# Debugger.net
KiCad netlist of a schematic drawn in Altium Designer
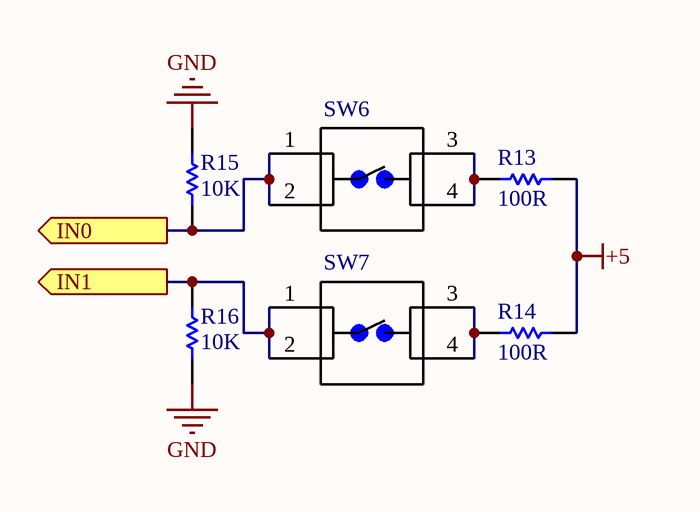
[diagram p0: Debugger.SchDoc]

(export (version "E")
  (design (tool "Eeschema 10.0.6"))
  (components
    (comp (ref "R13")
      (value "100R")
      (footprint "RESC0805(2012)_L")
      (description "100R 0.125W 1% 0805 (2012 Metric)  SMD")
      (fields (field (name "POWER") "0.125 W") (field (name "TOLERANCE") "1 %"))
      (libsource (lib "Altium Content Vault") (part "RES"))
    )
    (comp (ref "R14")
      (value "100R")
      (footprint "RESC0805(2012)_L")
      (description "100R 0.125W 1% 0805 (2012 Metric)  SMD")
      (fields (field (name "POWER") "0.125 W") (field (name "TOLERANCE") "1 %"))
      (libsource (lib "Altium Content Vault") (part "RES"))
    )
    (comp (ref "R15")
      (value "10K")
      (footprint "RESC0805(2012)_L")
      (description "10K2 0.125W 1% 0805 (2012 Metric)  SMD")
      (fields (field (name "TOLERANCE") "1 %") (field (name "POWER") "0.125 W"))
      (libsource (lib "Altium Content Vault") (part "RES"))
    )
    (comp (ref "R16")
      (value "10K")
      (footprint "RESC0805(2012)_L")
      (description "10K2 0.125W 1% 0805 (2012 Metric)  SMD")
      (fields (field (name "TOLERANCE") "1 %") (field (name "POWER") "0.125 W"))
      (libsource (lib "Altium Content Vault") (part "RES"))
    )
    (comp (ref "SW6")
      (value "1825910-7")
      (footprint "Switch 6mm 24V (NO)")
      (description "FSM4JAH=6MM TACT SWITCH, HIGH TEMP")
      (fields (field (name "MF") "TE Connectivity") (field (name "DIGI-KEY_PART_NUMBER") "450-1804-ND"))
      (libsource (lib "Husky Robotics Standard Library 2019-2020") (part "Switch 6mm 24V (NO)"))
    )
    (comp (ref "SW7")
      (value "1825910-7")
      (footprint "Switch 6mm 24V (NO)")
      (description "FSM4JAH=6MM TACT SWITCH, HIGH TEMP")
      (fields (field (name "MF") "TE Connectivity") (field (name "DIGI-KEY_PART_NUMBER") "450-1804-ND"))
      (libsource (lib "Husky Robotics Standard Library 2019-2020") (part "Switch 6mm 24V (NO)"))
    )
  )
  (nets
    (net (code "1") (name "+5") (class "Default")
      (node (ref "R13") (pin "1") (pinfunction "1_1") (pintype "passive"))
      (node (ref "R14") (pin "1") (pinfunction "1_1") (pintype "passive"))
    )
    (net (code "2") (name "/IN0") (class "Default")
      (node (ref "R15") (pin "1") (pinfunction "1_1") (pintype "passive"))
      (node (ref "SW6") (pin "1") (pinfunction "1_1") (pintype "passive"))
      (node (ref "SW6") (pin "2") (pinfunction "2_2") (pintype "passive"))
    )
    (net (code "3") (name "/IN1") (class "Default")
      (node (ref "R16") (pin "2") (pinfunction "2_2") (pintype "passive"))
      (node (ref "SW7") (pin "1") (pinfunction "1_1") (pintype "passive"))
      (node (ref "SW7") (pin "2") (pinfunction "2_2") (pintype "passive"))
    )
    (net (code "4") (name "GND") (class "Default")
      (node (ref "R15") (pin "2") (pinfunction "2_2") (pintype "passive"))
      (node (ref "R16") (pin "1") (pinfunction "1_1") (pintype "passive"))
    )
    (net (code "5") (name "Net-(R13-Pad2)") (class "Default")
      (node (ref "R13") (pin "2") (pinfunction "2_2") (pintype "passive"))
      (node (ref "SW6") (pin "3") (pinfunction "3_3") (pintype "passive"))
      (node (ref "SW6") (pin "4") (pinfunction "4_4") (pintype "passive"))
    )
    (net (code "6") (name "Net-(R14-Pad2)") (class "Default")
      (node (ref "R14") (pin "2") (pinfunction "2_2") (pintype "passive"))
      (node (ref "SW7") (pin "3") (pinfunction "3_3") (pintype "passive"))
      (node (ref "SW7") (pin "4") (pinfunction "4_4") (pintype "passive"))
    )
  )
)
